# NG2093_CAM_2Lane.net
KiCad netlist of a schematic drawn in Altium Designer
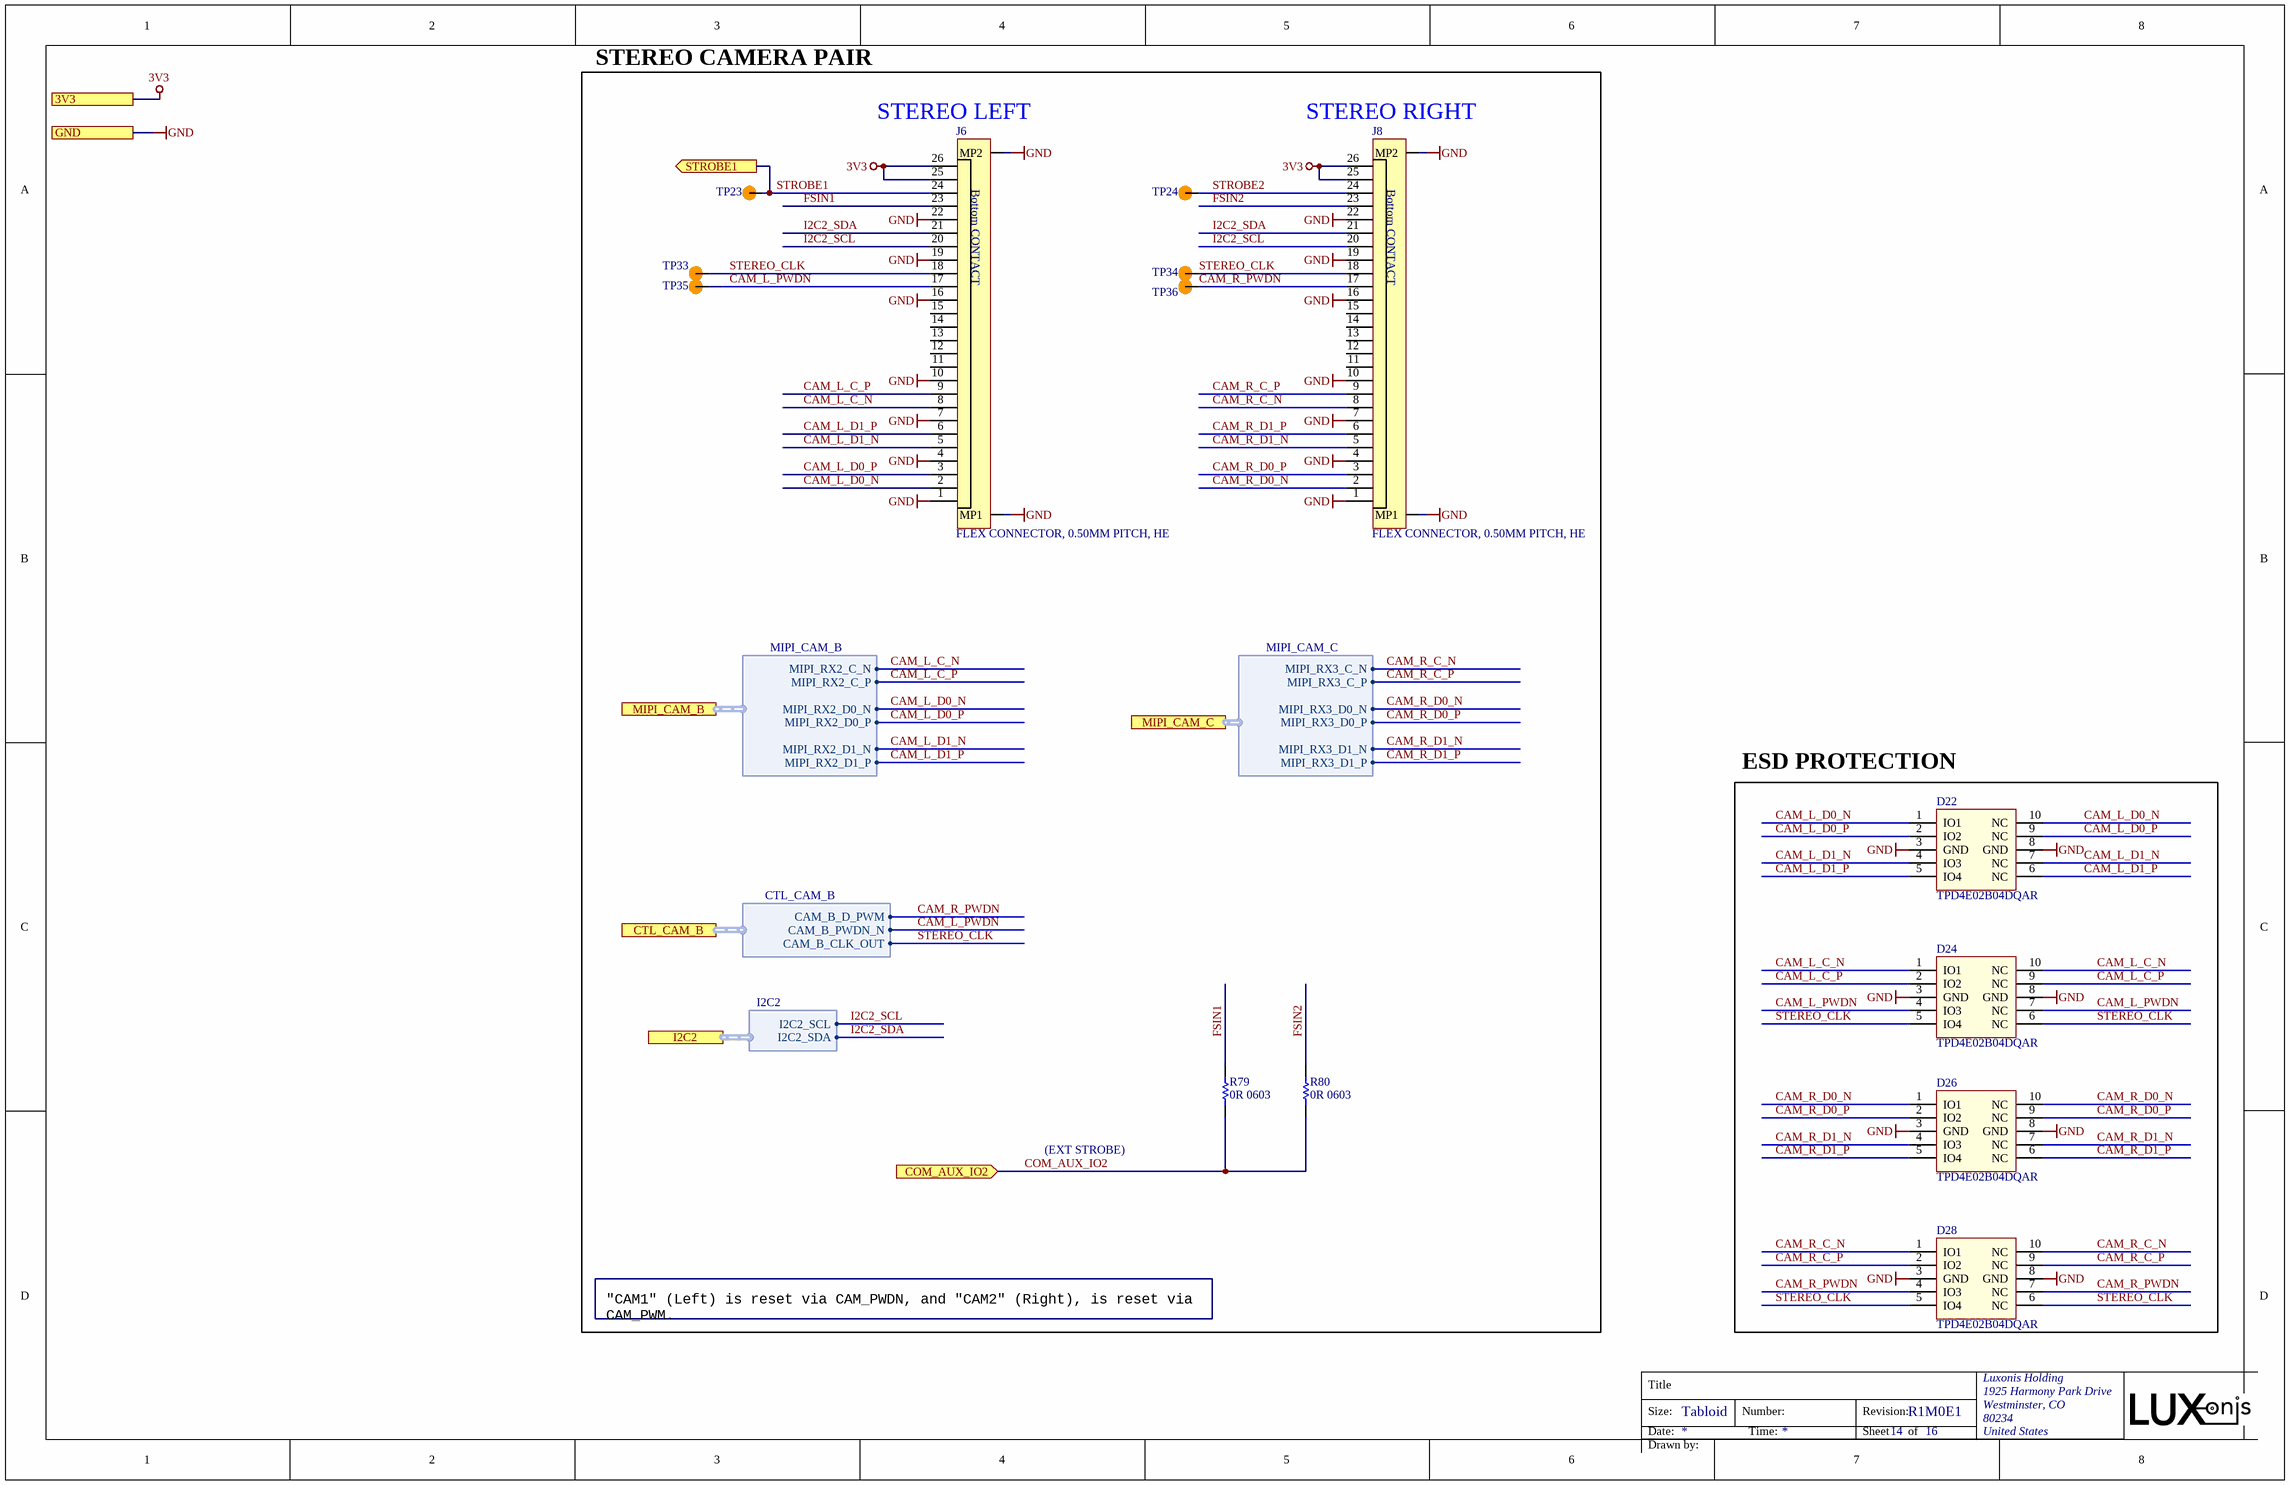
[diagram p0: NG2093_CAM_2Lane.SchDoc]

(export (version "E")
  (design (tool "Eeschema 10.0.6"))
  (components
    (comp (ref "D22")
      (value "TPD4E02B04DQAR")
      (footprint "TPD4E02B04DQAR")
      (libsource (lib "LuxonisMaster") (part "TPD4E02B04DQAR"))
    )
    (comp (ref "D24")
      (value "TPD4E02B04DQAR")
      (footprint "TPD4E02B04DQAR")
      (libsource (lib "LuxonisMaster") (part "TPD4E02B04DQAR"))
    )
    (comp (ref "D26")
      (value "TPD4E02B04DQAR")
      (footprint "TPD4E02B04DQAR")
      (libsource (lib "LuxonisMaster") (part "TPD4E02B04DQAR"))
    )
    (comp (ref "D28")
      (value "TPD4E02B04DQAR")
      (footprint "TPD4E02B04DQAR")
      (libsource (lib "LuxonisMaster") (part "TPD4E02B04DQAR"))
    )
    (comp (ref "J6")
      (value "FLEX CONNECTOR, 0.50MM PITCH, HE")
      (footprint "DM1090FFC:F32R-1A7H1-11026")
      (description "26 Position FFC, FPC Connector Contacts, Bottom 0.020\" (0.50mm) Surface Mount, Right Angle")
      (libsource (lib "DM1090FFC") (part "F32R-1A7H1-11026"))
    )
    (comp (ref "J8")
      (value "FLEX CONNECTOR, 0.50MM PITCH, HE")
      (footprint "DM1090FFC:F32R-1A7H1-11026")
      (description "26 Position FFC, FPC Connector Contacts, Bottom 0.020\" (0.50mm) Surface Mount, Right Angle")
      (libsource (lib "DM1090FFC") (part "F32R-1A7H1-11026"))
    )
    (comp (ref "R79")
      (value "0R 0603")
      (footprint "RESC0603(1608)_N")
      (fields (field (name "TOLERANCE") "5%"))
      (libsource (lib "LuxonisMaster") (part "CRCW06030000Z0EA"))
    )
    (comp (ref "R80")
      (value "0R 0603")
      (footprint "RESC0603(1608)_N")
      (fields (field (name "TOLERANCE") "5%"))
      (libsource (lib "LuxonisMaster") (part "CRCW06030000Z0EA"))
    )
    (comp (ref "TP23")
      (value "TP100_200_NS")
      (footprint "TP100_200_NS")
      (libsource (lib "LuxonisMaster") (part "TEST_POINT"))
    )
    (comp (ref "TP24")
      (value "TP100_200_NS")
      (footprint "TP100_200_NS")
      (libsource (lib "LuxonisMaster") (part "TEST_POINT"))
    )
    (comp (ref "TP33")
      (value "TP100_200_NS")
      (footprint "TP100_200_NS")
      (libsource (lib "LuxonisMaster") (part "TEST_POINT"))
    )
    (comp (ref "TP34")
      (value "TP100_200_NS")
      (footprint "TP100_200_NS")
      (libsource (lib "LuxonisMaster") (part "TEST_POINT"))
    )
    (comp (ref "TP35")
      (value "TP100_200_NS")
      (footprint "TP100_200_NS")
      (libsource (lib "LuxonisMaster") (part "TEST_POINT"))
    )
    (comp (ref "TP36")
      (value "TP100_200_NS")
      (footprint "TP100_200_NS")
      (libsource (lib "LuxonisMaster") (part "TEST_POINT"))
    )
  )
  (nets
    (net (code "5") (name "/CAM_L_C_N") (class "Default")
      (node (ref "D24") (pin "1") (pinfunction "IO1_1") (pintype "passive"))
      (node (ref "D24") (pin "10") (pinfunction "NC_10") (pintype "passive"))
      (node (ref "J6") (pin "8") (pinfunction "8_8") (pintype "passive"))
    )
    (net (code "6") (name "/CAM_L_C_P") (class "Default")
      (node (ref "D24") (pin "2") (pinfunction "IO2_2") (pintype "passive"))
      (node (ref "D24") (pin "9") (pinfunction "NC_9") (pintype "passive"))
      (node (ref "J6") (pin "9") (pinfunction "9_9") (pintype "passive"))
    )
    (net (code "7") (name "/CAM_L_D0_N") (class "Default")
      (node (ref "D22") (pin "1") (pinfunction "IO1_1") (pintype "passive"))
      (node (ref "D22") (pin "10") (pinfunction "NC_10") (pintype "passive"))
      (node (ref "J6") (pin "2") (pinfunction "2_2") (pintype "passive"))
    )
    (net (code "8") (name "/CAM_L_D0_P") (class "Default")
      (node (ref "D22") (pin "2") (pinfunction "IO2_2") (pintype "passive"))
      (node (ref "D22") (pin "9") (pinfunction "NC_9") (pintype "passive"))
      (node (ref "J6") (pin "3") (pinfunction "3_3") (pintype "passive"))
    )
    (net (code "9") (name "/CAM_L_D1_N") (class "Default")
      (node (ref "D22") (pin "4") (pinfunction "IO3_4") (pintype "passive"))
      (node (ref "D22") (pin "7") (pinfunction "NC_7") (pintype "passive"))
      (node (ref "J6") (pin "5") (pinfunction "5_5") (pintype "passive"))
    )
    (net (code "10") (name "/CAM_L_D1_P") (class "Default")
      (node (ref "D22") (pin "5") (pinfunction "IO4_5") (pintype "passive"))
      (node (ref "D22") (pin "6") (pinfunction "NC_6") (pintype "passive"))
      (node (ref "J6") (pin "6") (pinfunction "6_6") (pintype "passive"))
    )
    (net (code "11") (name "/CAM_L_PWDN") (class "Default")
      (node (ref "D24") (pin "4") (pinfunction "IO3_4") (pintype "passive"))
      (node (ref "D24") (pin "7") (pinfunction "NC_7") (pintype "passive"))
      (node (ref "J6") (pin "17") (pinfunction "17_17") (pintype "passive"))
      (node (ref "TP35") (pin "1") (pintype "passive"))
    )
    (net (code "12") (name "/CAM_R_C_N") (class "Default")
      (node (ref "D28") (pin "1") (pinfunction "IO1_1") (pintype "passive"))
      (node (ref "D28") (pin "10") (pinfunction "NC_10") (pintype "passive"))
      (node (ref "J8") (pin "8") (pinfunction "8_8") (pintype "passive"))
    )
    (net (code "13") (name "/CAM_R_C_P") (class "Default")
      (node (ref "D28") (pin "2") (pinfunction "IO2_2") (pintype "passive"))
      (node (ref "D28") (pin "9") (pinfunction "NC_9") (pintype "passive"))
      (node (ref "J8") (pin "9") (pinfunction "9_9") (pintype "passive"))
    )
    (net (code "14") (name "/CAM_R_D0_N") (class "Default")
      (node (ref "D26") (pin "1") (pinfunction "IO1_1") (pintype "passive"))
      (node (ref "D26") (pin "10") (pinfunction "NC_10") (pintype "passive"))
      (node (ref "J8") (pin "2") (pinfunction "2_2") (pintype "passive"))
    )
    (net (code "15") (name "/CAM_R_D0_P") (class "Default")
      (node (ref "D26") (pin "2") (pinfunction "IO2_2") (pintype "passive"))
      (node (ref "D26") (pin "9") (pinfunction "NC_9") (pintype "passive"))
      (node (ref "J8") (pin "3") (pinfunction "3_3") (pintype "passive"))
    )
    (net (code "16") (name "/CAM_R_D1_N") (class "Default")
      (node (ref "D26") (pin "4") (pinfunction "IO3_4") (pintype "passive"))
      (node (ref "D26") (pin "7") (pinfunction "NC_7") (pintype "passive"))
      (node (ref "J8") (pin "5") (pinfunction "5_5") (pintype "passive"))
    )
    (net (code "17") (name "/CAM_R_D1_P") (class "Default")
      (node (ref "D26") (pin "5") (pinfunction "IO4_5") (pintype "passive"))
      (node (ref "D26") (pin "6") (pinfunction "NC_6") (pintype "passive"))
      (node (ref "J8") (pin "6") (pinfunction "6_6") (pintype "passive"))
    )
    (net (code "18") (name "/CAM_R_PWDN") (class "Default")
      (node (ref "D28") (pin "4") (pinfunction "IO3_4") (pintype "passive"))
      (node (ref "D28") (pin "7") (pinfunction "NC_7") (pintype "passive"))
      (node (ref "J8") (pin "17") (pinfunction "17_17") (pintype "passive"))
      (node (ref "TP36") (pin "1") (pintype "passive"))
    )
    (net (code "19") (name "/COM_AUX_IO2") (class "Default")
      (node (ref "R79") (pin "1") (pinfunction "1_1") (pintype "passive"))
      (node (ref "R80") (pin "1") (pinfunction "1_1") (pintype "passive"))
    )
    (net (code "20") (name "/FSIN1") (class "Default")
      (node (ref "J6") (pin "23") (pinfunction "23_23") (pintype "passive"))
      (node (ref "R79") (pin "2") (pinfunction "2_2") (pintype "passive"))
    )
    (net (code "21") (name "/FSIN2") (class "Default")
      (node (ref "J8") (pin "23") (pinfunction "23_23") (pintype "passive"))
      (node (ref "R80") (pin "2") (pinfunction "2_2") (pintype "passive"))
    )
    (net (code "22") (name "/I2C2_SCL") (class "Default")
      (node (ref "J6") (pin "20") (pinfunction "20_20") (pintype "passive"))
      (node (ref "J8") (pin "20") (pinfunction "20_20") (pintype "passive"))
    )
    (net (code "23") (name "/I2C2_SDA") (class "Default")
      (node (ref "J6") (pin "21") (pinfunction "21_21") (pintype "passive"))
      (node (ref "J8") (pin "21") (pinfunction "21_21") (pintype "passive"))
    )
    (net (code "24") (name "/STEREO_CLK") (class "Default")
      (node (ref "D24") (pin "5") (pinfunction "IO4_5") (pintype "passive"))
      (node (ref "D24") (pin "6") (pinfunction "NC_6") (pintype "passive"))
      (node (ref "D28") (pin "5") (pinfunction "IO4_5") (pintype "passive"))
      (node (ref "D28") (pin "6") (pinfunction "NC_6") (pintype "passive"))
      (node (ref "J6") (pin "18") (pinfunction "18_18") (pintype "passive"))
      (node (ref "J8") (pin "18") (pinfunction "18_18") (pintype "passive"))
      (node (ref "TP33") (pin "1") (pintype "passive"))
      (node (ref "TP34") (pin "1") (pintype "passive"))
    )
    (net (code "25") (name "/STROBE1") (class "Default")
      (node (ref "J6") (pin "24") (pinfunction "24_24") (pintype "passive"))
      (node (ref "TP23") (pin "1") (pintype "passive"))
    )
    (net (code "26") (name "/STROBE2") (class "Default")
      (node (ref "J8") (pin "24") (pinfunction "24_24") (pintype "passive"))
      (node (ref "TP24") (pin "1") (pintype "passive"))
    )
    (net (code "31") (name "3V3") (class "Default")
      (node (ref "J6") (pin "25") (pinfunction "25_25") (pintype "passive"))
      (node (ref "J6") (pin "26") (pinfunction "26_26") (pintype "passive"))
      (node (ref "J8") (pin "25") (pinfunction "25_25") (pintype "passive"))
      (node (ref "J8") (pin "26") (pinfunction "26_26") (pintype "passive"))
    )
    (net (code "32") (name "GND") (class "Default")
      (node (ref "D22") (pin "3") (pinfunction "GND_3") (pintype "passive"))
      (node (ref "D22") (pin "8") (pinfunction "GND_8") (pintype "passive"))
      (node (ref "D24") (pin "3") (pinfunction "GND_3") (pintype "passive"))
      (node (ref "D24") (pin "8") (pinfunction "GND_8") (pintype "passive"))
      (node (ref "D26") (pin "3") (pinfunction "GND_3") (pintype "passive"))
      (node (ref "D26") (pin "8") (pinfunction "GND_8") (pintype "passive"))
      (node (ref "D28") (pin "3") (pinfunction "GND_3") (pintype "passive"))
      (node (ref "D28") (pin "8") (pinfunction "GND_8") (pintype "passive"))
      (node (ref "J6") (pin "1") (pinfunction "1_1") (pintype "passive"))
      (node (ref "J6") (pin "10") (pinfunction "10_10") (pintype "passive"))
      (node (ref "J6") (pin "16") (pinfunction "16_16") (pintype "passive"))
      (node (ref "J6") (pin "19") (pinfunction "19_19") (pintype "passive"))
      (node (ref "J6") (pin "22") (pinfunction "22_22") (pintype "passive"))
      (node (ref "J6") (pin "4") (pinfunction "4_4") (pintype "passive"))
      (node (ref "J6") (pin "7") (pinfunction "7_7") (pintype "passive"))
      (node (ref "J6") (pin "MP1") (pinfunction "MP1_MP1") (pintype "passive"))
      (node (ref "J6") (pin "MP2") (pinfunction "MP2_MP2") (pintype "passive"))
      (node (ref "J8") (pin "1") (pinfunction "1_1") (pintype "passive"))
      (node (ref "J8") (pin "10") (pinfunction "10_10") (pintype "passive"))
      (node (ref "J8") (pin "16") (pinfunction "16_16") (pintype "passive"))
      (node (ref "J8") (pin "19") (pinfunction "19_19") (pintype "passive"))
      (node (ref "J8") (pin "22") (pinfunction "22_22") (pintype "passive"))
      (node (ref "J8") (pin "4") (pinfunction "4_4") (pintype "passive"))
      (node (ref "J8") (pin "7") (pinfunction "7_7") (pintype "passive"))
      (node (ref "J8") (pin "MP1") (pinfunction "MP1_MP1") (pintype "passive"))
      (node (ref "J8") (pin "MP2") (pinfunction "MP2_MP2") (pintype "passive"))
    )
    (net (code "33") (name "unconnected-(J6-Pad11)") (class "Default")
      (node (ref "J6") (pin "11") (pinfunction "11_11") (pintype "passive"))
    )
    (net (code "34") (name "unconnected-(J6-Pad12)") (class "Default")
      (node (ref "J6") (pin "12") (pinfunction "12_12") (pintype "passive"))
    )
    (net (code "35") (name "unconnected-(J6-Pad13)") (class "Default")
      (node (ref "J6") (pin "13") (pinfunction "13_13") (pintype "passive"))
    )
    (net (code "36") (name "unconnected-(J6-Pad14)") (class "Default")
      (node (ref "J6") (pin "14") (pinfunction "14_14") (pintype "passive"))
    )
    (net (code "37") (name "unconnected-(J6-Pad15)") (class "Default")
      (node (ref "J6") (pin "15") (pinfunction "15_15") (pintype "passive"))
    )
    (net (code "38") (name "unconnected-(J8-Pad11)") (class "Default")
      (node (ref "J8") (pin "11") (pinfunction "11_11") (pintype "passive"))
    )
    (net (code "39") (name "unconnected-(J8-Pad12)") (class "Default")
      (node (ref "J8") (pin "12") (pinfunction "12_12") (pintype "passive"))
    )
    (net (code "40") (name "unconnected-(J8-Pad13)") (class "Default")
      (node (ref "J8") (pin "13") (pinfunction "13_13") (pintype "passive"))
    )
    (net (code "41") (name "unconnected-(J8-Pad14)") (class "Default")
      (node (ref "J8") (pin "14") (pinfunction "14_14") (pintype "passive"))
    )
    (net (code "42") (name "unconnected-(J8-Pad15)") (class "Default")
      (node (ref "J8") (pin "15") (pinfunction "15_15") (pintype "passive"))
    )
  )
)
